# 05_Connector.net
KiCad netlist of a schematic drawn in Altium Designer
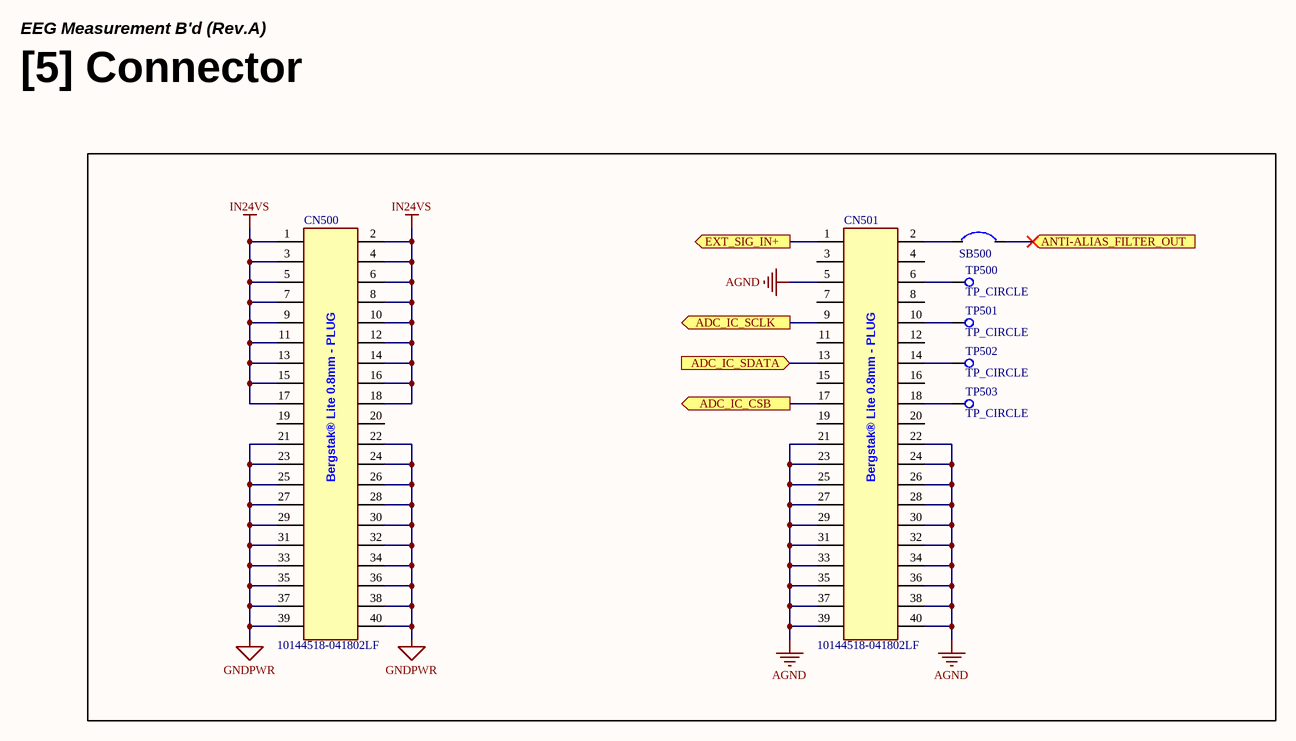
[diagram p0: 05_Connector.SchDoc]

(export (version "E")
  (design (tool "Eeschema 10.0.6"))
  (components
    (comp (ref "CN500")
      (value "10144518-041802LF")
      (footprint "CON_BergStak-Lite(0.8mm)_PLUG-40P(10144518-041802LF)")
      (fields (field (name "LCSC PART #") "C5410298"))
      (libsource (lib "Arkx") (part "CON_BergStak-Lite(0.8mm)_PLUG-40P(10144518-041802LF)"))
    )
    (comp (ref "CN501")
      (value "10144518-041802LF")
      (footprint "CON_BergStak-Lite(0.8mm)_PLUG-40P(10144518-041802LF)")
      (fields (field (name "LCSC PART #") "C5410298"))
      (libsource (lib "Arkx") (part "CON_BergStak-Lite(0.8mm)_PLUG-40P(10144518-041802LF)"))
    )
    (comp (ref "SB500")
      (value "SB")
      (footprint "SB (Solder-Bridge)")
      (description "SB_Solder-Bridge")
      (libsource (lib "Arkx") (part "SB_Solder-Bridge"))
    )
    (comp (ref "TP500")
      (value "TP_CIRCLE")
      (footprint "TP Circle")
      (libsource (lib "Arkx") (part "TP_CIRCLE"))
    )
    (comp (ref "TP501")
      (value "TP_CIRCLE")
      (footprint "TP Circle")
      (libsource (lib "Arkx") (part "TP_CIRCLE"))
    )
    (comp (ref "TP502")
      (value "TP_CIRCLE")
      (footprint "TP Circle")
      (libsource (lib "Arkx") (part "TP_CIRCLE"))
    )
    (comp (ref "TP503")
      (value "TP_CIRCLE")
      (footprint "TP Circle")
      (libsource (lib "Arkx") (part "TP_CIRCLE"))
    )
  )
  (nets
    (net (code "1") (name "/ADC_IC_CSB") (class "Default")
      (node (ref "CN501") (pin "17") (pinfunction "17_17") (pintype "passive"))
    )
    (net (code "2") (name "/ADC_IC_SCLK") (class "Default")
      (node (ref "CN501") (pin "9") (pinfunction "9_9") (pintype "passive"))
    )
    (net (code "3") (name "/ADC_IC_SDATA") (class "Default")
      (node (ref "CN501") (pin "13") (pinfunction "13_13") (pintype "passive"))
    )
    (net (code "4") (name "/ANTI-ALIAS_FILTER_OUT") (class "Default")
      (node (ref "SB500") (pin "2") (pinfunction "2_2") (pintype "passive+no_connect"))
    )
    (net (code "5") (name "/EXT_SIG_IN+") (class "Default")
      (node (ref "CN501") (pin "1") (pinfunction "1_1") (pintype "passive"))
    )
    (net (code "6") (name "AGND") (class "Default")
      (node (ref "CN501") (pin "21") (pinfunction "21_21") (pintype "passive"))
      (node (ref "CN501") (pin "22") (pinfunction "22_22") (pintype "passive"))
      (node (ref "CN501") (pin "23") (pinfunction "23_23") (pintype "passive"))
      (node (ref "CN501") (pin "24") (pinfunction "24_24") (pintype "passive"))
      (node (ref "CN501") (pin "25") (pinfunction "25_25") (pintype "passive"))
      (node (ref "CN501") (pin "26") (pinfunction "26_26") (pintype "passive"))
      (node (ref "CN501") (pin "27") (pinfunction "27_27") (pintype "passive"))
      (node (ref "CN501") (pin "28") (pinfunction "28_28") (pintype "passive"))
      (node (ref "CN501") (pin "29") (pinfunction "29_29") (pintype "passive"))
      (node (ref "CN501") (pin "30") (pinfunction "30_30") (pintype "passive"))
      (node (ref "CN501") (pin "31") (pinfunction "31_31") (pintype "passive"))
      (node (ref "CN501") (pin "32") (pinfunction "32_32") (pintype "passive"))
      (node (ref "CN501") (pin "33") (pinfunction "33_33") (pintype "passive"))
      (node (ref "CN501") (pin "34") (pinfunction "34_34") (pintype "passive"))
      (node (ref "CN501") (pin "35") (pinfunction "35_35") (pintype "passive"))
      (node (ref "CN501") (pin "36") (pinfunction "36_36") (pintype "passive"))
      (node (ref "CN501") (pin "37") (pinfunction "37_37") (pintype "passive"))
      (node (ref "CN501") (pin "38") (pinfunction "38_38") (pintype "passive"))
      (node (ref "CN501") (pin "39") (pinfunction "39_39") (pintype "passive"))
      (node (ref "CN501") (pin "40") (pinfunction "40_40") (pintype "passive"))
      (node (ref "CN501") (pin "5") (pinfunction "5_5") (pintype "passive"))
    )
    (net (code "7") (name "GNDPWR") (class "Default")
      (node (ref "CN500") (pin "21") (pinfunction "21_21") (pintype "passive"))
      (node (ref "CN500") (pin "22") (pinfunction "22_22") (pintype "passive"))
      (node (ref "CN500") (pin "23") (pinfunction "23_23") (pintype "passive"))
      (node (ref "CN500") (pin "24") (pinfunction "24_24") (pintype "passive"))
      (node (ref "CN500") (pin "25") (pinfunction "25_25") (pintype "passive"))
      (node (ref "CN500") (pin "26") (pinfunction "26_26") (pintype "passive"))
      (node (ref "CN500") (pin "27") (pinfunction "27_27") (pintype "passive"))
      (node (ref "CN500") (pin "28") (pinfunction "28_28") (pintype "passive"))
      (node (ref "CN500") (pin "29") (pinfunction "29_29") (pintype "passive"))
      (node (ref "CN500") (pin "30") (pinfunction "30_30") (pintype "passive"))
      (node (ref "CN500") (pin "31") (pinfunction "31_31") (pintype "passive"))
      (node (ref "CN500") (pin "32") (pinfunction "32_32") (pintype "passive"))
      (node (ref "CN500") (pin "33") (pinfunction "33_33") (pintype "passive"))
      (node (ref "CN500") (pin "34") (pinfunction "34_34") (pintype "passive"))
      (node (ref "CN500") (pin "35") (pinfunction "35_35") (pintype "passive"))
      (node (ref "CN500") (pin "36") (pinfunction "36_36") (pintype "passive"))
      (node (ref "CN500") (pin "37") (pinfunction "37_37") (pintype "passive"))
      (node (ref "CN500") (pin "38") (pinfunction "38_38") (pintype "passive"))
      (node (ref "CN500") (pin "39") (pinfunction "39_39") (pintype "passive"))
      (node (ref "CN500") (pin "40") (pinfunction "40_40") (pintype "passive"))
    )
    (net (code "8") (name "IN24VS") (class "Default")
      (node (ref "CN500") (pin "1") (pinfunction "1_1") (pintype "passive"))
      (node (ref "CN500") (pin "10") (pinfunction "10_10") (pintype "passive"))
      (node (ref "CN500") (pin "11") (pinfunction "11_11") (pintype "passive"))
      (node (ref "CN500") (pin "12") (pinfunction "12_12") (pintype "passive"))
      (node (ref "CN500") (pin "13") (pinfunction "13_13") (pintype "passive"))
      (node (ref "CN500") (pin "14") (pinfunction "14_14") (pintype "passive"))
      (node (ref "CN500") (pin "15") (pinfunction "15_15") (pintype "passive"))
      (node (ref "CN500") (pin "16") (pinfunction "16_16") (pintype "passive"))
      (node (ref "CN500") (pin "17") (pinfunction "17_17") (pintype "passive"))
      (node (ref "CN500") (pin "18") (pinfunction "18_18") (pintype "passive"))
      (node (ref "CN500") (pin "2") (pinfunction "2_2") (pintype "passive"))
      (node (ref "CN500") (pin "3") (pinfunction "3_3") (pintype "passive"))
      (node (ref "CN500") (pin "4") (pinfunction "4_4") (pintype "passive"))
      (node (ref "CN500") (pin "5") (pinfunction "5_5") (pintype "passive"))
      (node (ref "CN500") (pin "6") (pinfunction "6_6") (pintype "passive"))
      (node (ref "CN500") (pin "7") (pinfunction "7_7") (pintype "passive"))
      (node (ref "CN500") (pin "8") (pinfunction "8_8") (pintype "passive"))
      (node (ref "CN500") (pin "9") (pinfunction "9_9") (pintype "passive"))
    )
    (net (code "9") (name "Net-(CN501-Pad2)") (class "Default")
      (node (ref "CN501") (pin "2") (pinfunction "2_2") (pintype "passive"))
      (node (ref "SB500") (pin "1") (pinfunction "1_1") (pintype "passive"))
    )
    (net (code "10") (name "Net-(TP500-TP)") (class "Default")
      (node (ref "CN501") (pin "6") (pinfunction "6_6") (pintype "passive"))
      (node (ref "TP500") (pin "1") (pinfunction "TP_1") (pintype "passive"))
    )
    (net (code "11") (name "Net-(TP501-TP)") (class "Default")
      (node (ref "CN501") (pin "10") (pinfunction "10_10") (pintype "passive"))
      (node (ref "TP501") (pin "1") (pinfunction "TP_1") (pintype "passive"))
    )
    (net (code "12") (name "Net-(TP502-TP)") (class "Default")
      (node (ref "CN501") (pin "14") (pinfunction "14_14") (pintype "passive"))
      (node (ref "TP502") (pin "1") (pinfunction "TP_1") (pintype "passive"))
    )
    (net (code "13") (name "Net-(TP503-TP)") (class "Default")
      (node (ref "CN501") (pin "18") (pinfunction "18_18") (pintype "passive"))
      (node (ref "TP503") (pin "1") (pinfunction "TP_1") (pintype "passive"))
    )
    (net (code "14") (name "unconnected-(CN500-Pad19)") (class "Default")
      (node (ref "CN500") (pin "19") (pinfunction "19_19") (pintype "passive"))
    )
    (net (code "15") (name "unconnected-(CN500-Pad20)") (class "Default")
      (node (ref "CN500") (pin "20") (pinfunction "20_20") (pintype "passive"))
    )
    (net (code "16") (name "unconnected-(CN501-Pad3)") (class "Default")
      (node (ref "CN501") (pin "3") (pinfunction "3_3") (pintype "passive"))
    )
    (net (code "17") (name "unconnected-(CN501-Pad4)") (class "Default")
      (node (ref "CN501") (pin "4") (pinfunction "4_4") (pintype "passive"))
    )
    (net (code "18") (name "unconnected-(CN501-Pad7)") (class "Default")
      (node (ref "CN501") (pin "7") (pinfunction "7_7") (pintype "passive"))
    )
    (net (code "19") (name "unconnected-(CN501-Pad8)") (class "Default")
      (node (ref "CN501") (pin "8") (pinfunction "8_8") (pintype "passive"))
    )
    (net (code "20") (name "unconnected-(CN501-Pad11)") (class "Default")
      (node (ref "CN501") (pin "11") (pinfunction "11_11") (pintype "passive"))
    )
    (net (code "21") (name "unconnected-(CN501-Pad12)") (class "Default")
      (node (ref "CN501") (pin "12") (pinfunction "12_12") (pintype "passive"))
    )
    (net (code "22") (name "unconnected-(CN501-Pad15)") (class "Default")
      (node (ref "CN501") (pin "15") (pinfunction "15_15") (pintype "passive"))
    )
    (net (code "23") (name "unconnected-(CN501-Pad16)") (class "Default")
      (node (ref "CN501") (pin "16") (pinfunction "16_16") (pintype "passive"))
    )
    (net (code "24") (name "unconnected-(CN501-Pad19)") (class "Default")
      (node (ref "CN501") (pin "19") (pinfunction "19_19") (pintype "passive"))
    )
    (net (code "25") (name "unconnected-(CN501-Pad20)") (class "Default")
      (node (ref "CN501") (pin "20") (pinfunction "20_20") (pintype "passive"))
    )
  )
)
